# rooftop_reflector_v1_2.net
KiCad netlist of a schematic drawn in EAGLE
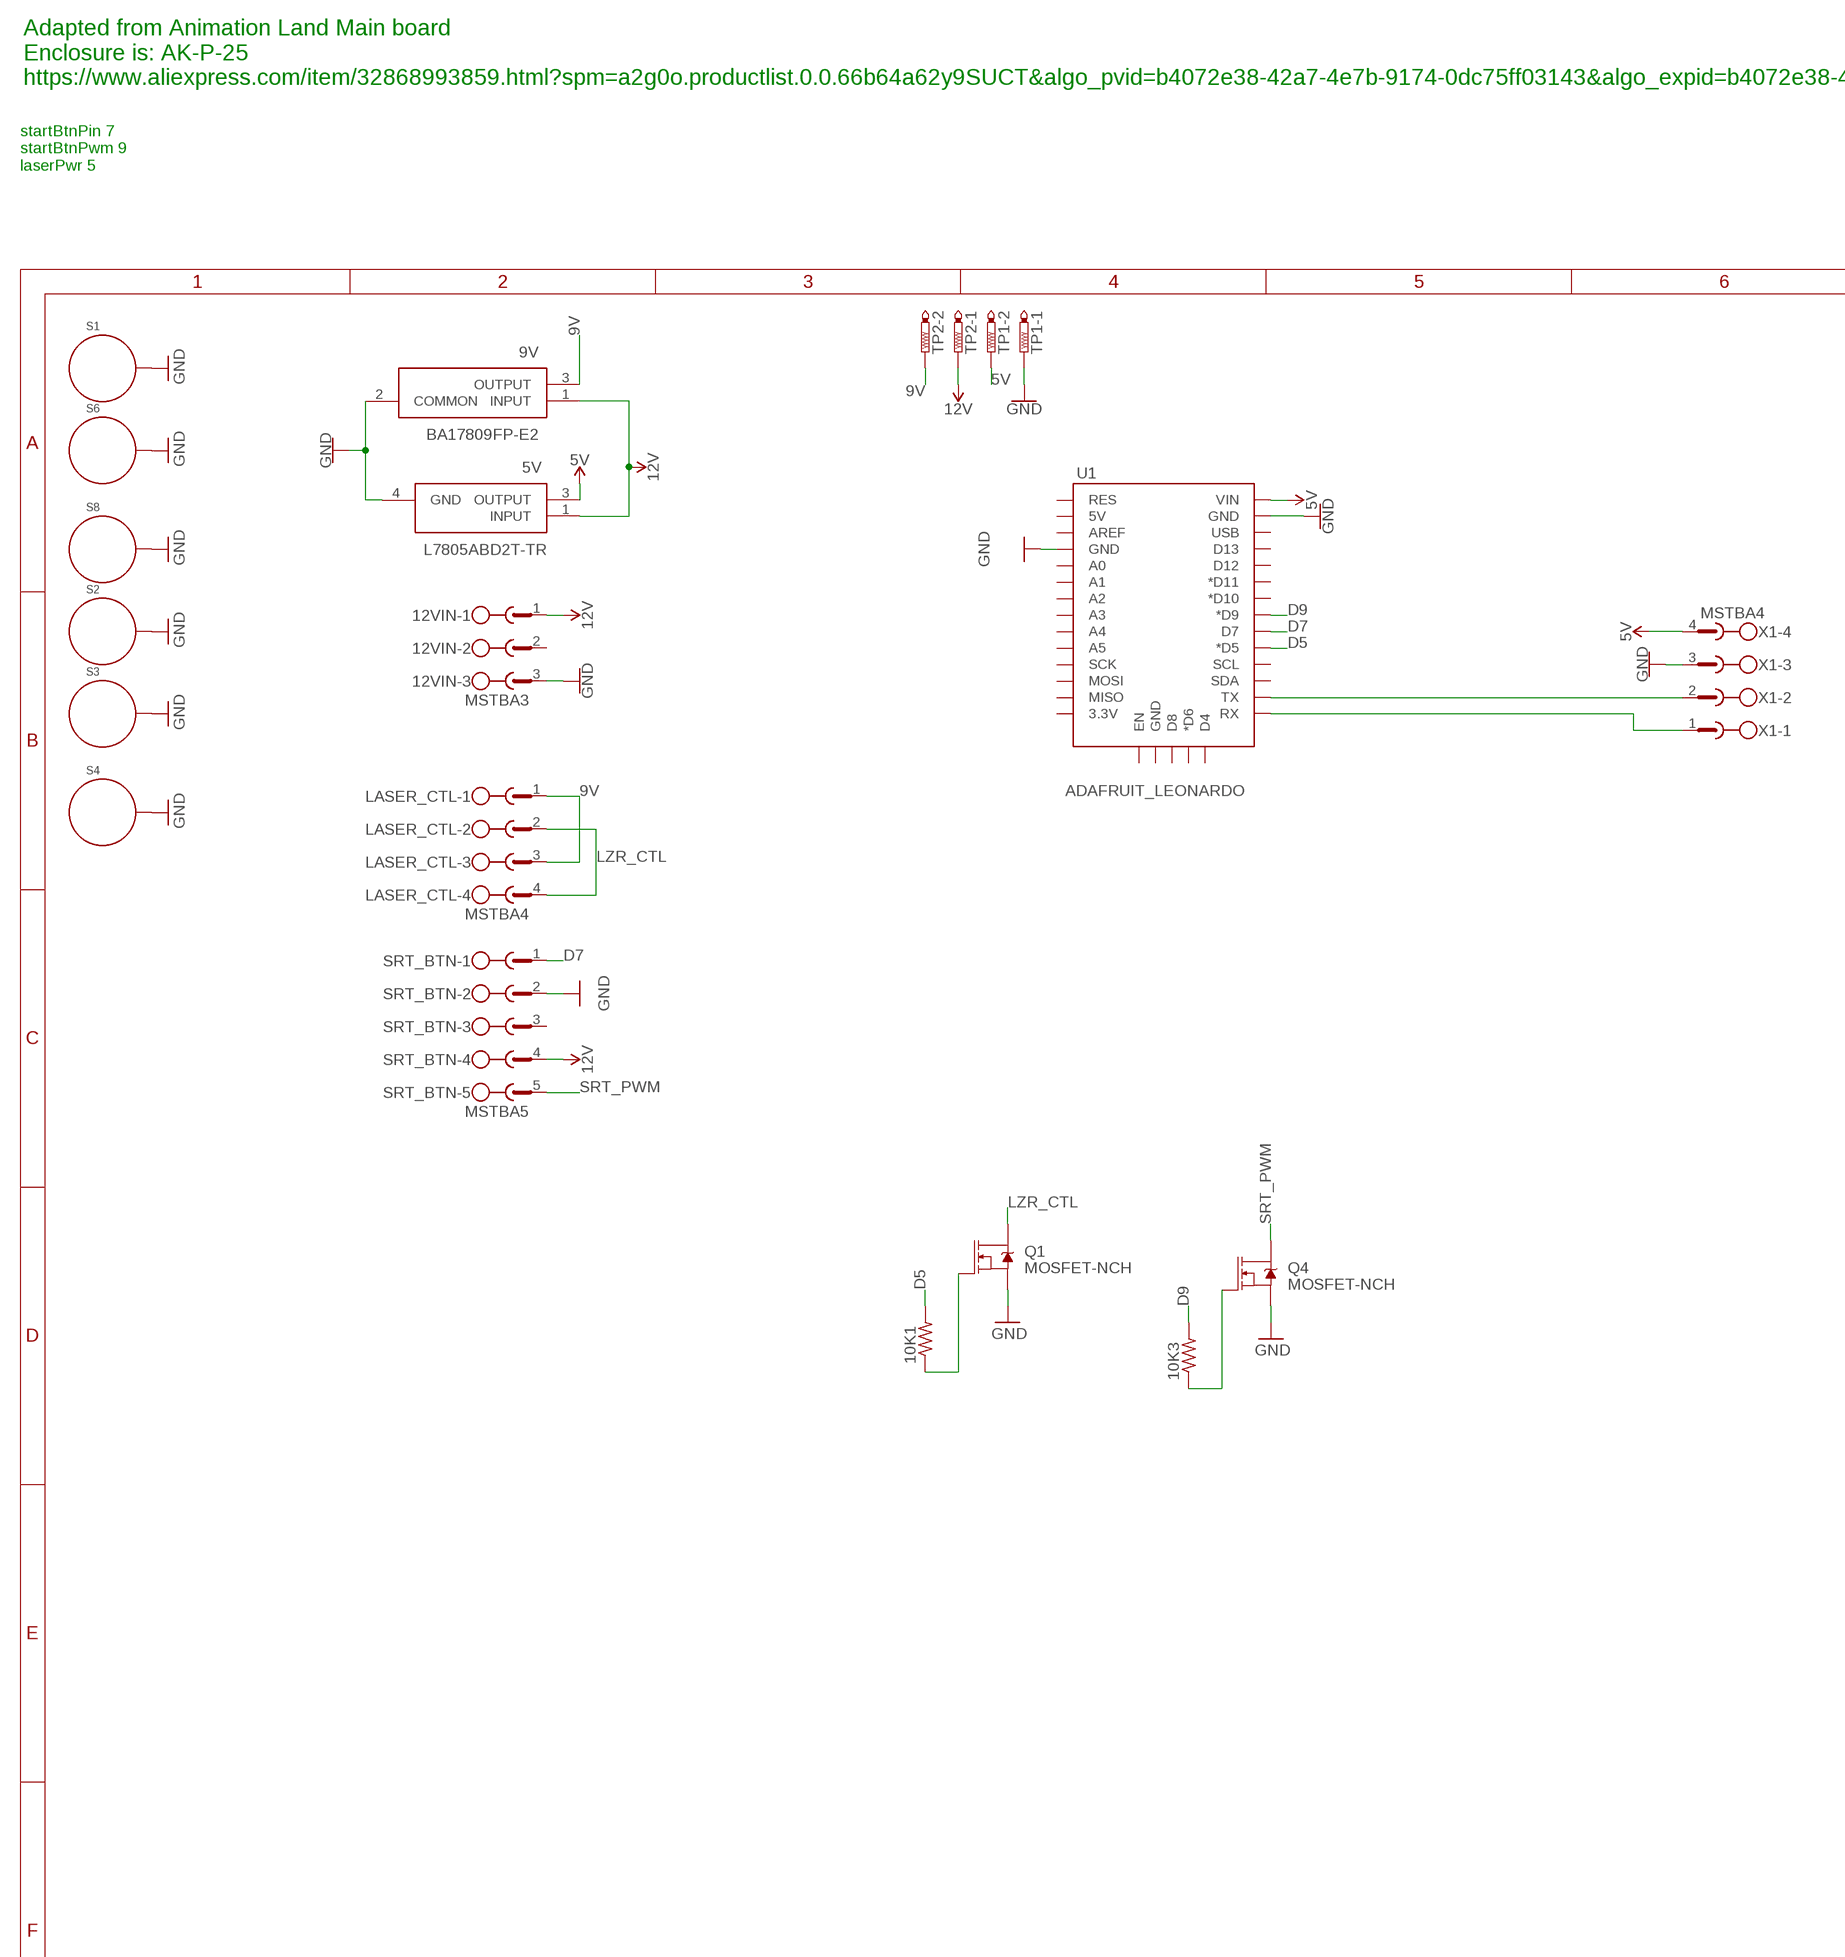
[diagram p0: schematic, sheet 1, part 1 of 2]
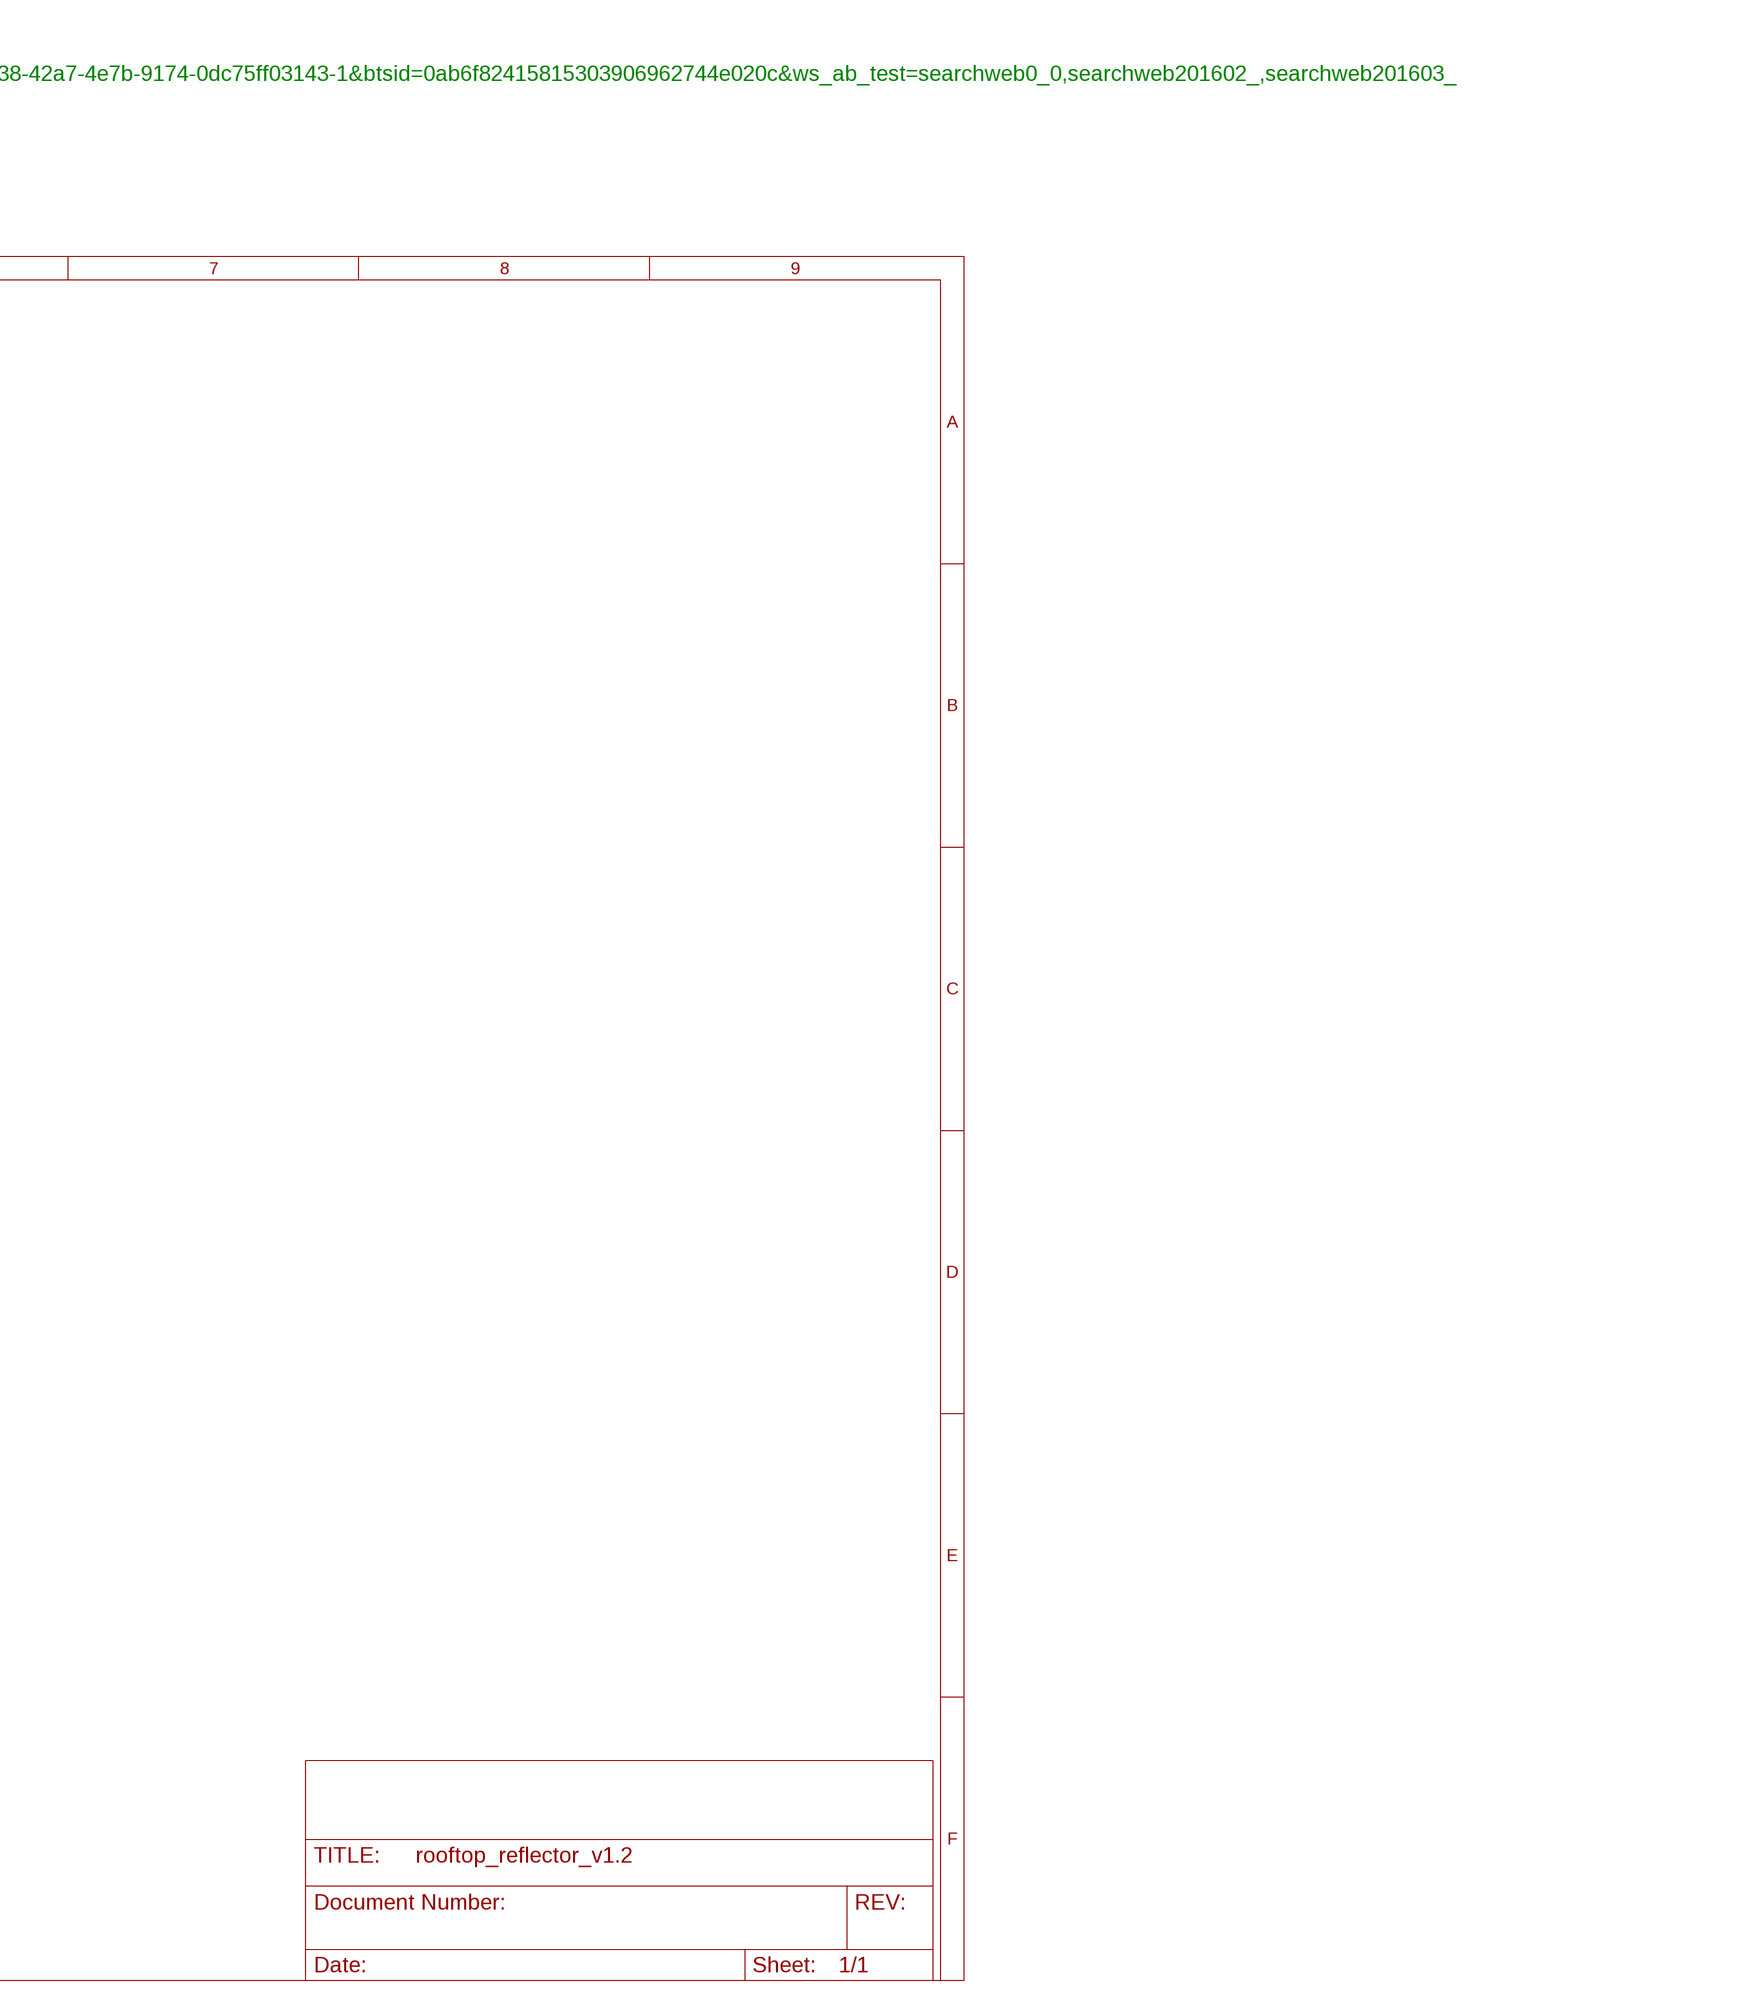
[diagram p1: schematic, sheet 1, part 2 of 2]

(export (version "E")
  (design (tool "Eeschema 10.0.6"))
  (components
    (comp (ref "5V")
      (value "L7805ABD2T-TR")
      (footprint "eagle-import:D2PAK-STB35NF10T4")
      (fields (field (name "MOUSER_PART_NUMBER") "511-L7805ABD2T-TR"))
      (libsource (lib "eagle-import") (part "L7805ABD2T-TR"))
    )
    (comp (ref "9V")
      (value "BA17809FP-E2")
      (footprint "eagle-import:BA17809FPE2")
      (fields (field (name "MOUSER_PART_NUMBER") "755-BA17809FP-E2"))
      (libsource (lib "eagle-import") (part "BA17809FP-E2"))
    )
    (comp (ref "10K1")
      (value "R-US_M0805")
      (footprint "eagle-import:M0805")
      (libsource (lib "eagle-import") (part "R-US_M0805"))
    )
    (comp (ref "10K3")
      (value "R-US_M0805")
      (footprint "eagle-import:M0805")
      (libsource (lib "eagle-import") (part "R-US_M0805"))
    )
    (comp (ref "12VIN")
      (value "MSTBA3")
      (footprint "eagle-import:MSTBA3")
      (fields (field (name "MF") "FARNELL") (field (name "MPN") "1757255"))
      (libsource (lib "eagle-import") (part "MSTBA3"))
    )
    (comp (ref "LASER_CTL")
      (value "MSTBA4")
      (footprint "eagle-import:MSTBA4")
      (fields (field (name "MF") "FARNELL") (field (name "MPN") "1757268"))
      (libsource (lib "eagle-import") (part "MSTBA4"))
    )
    (comp (ref "Q1")
      (value "MOSFET-NCH")
      (footprint "eagle-import:SO-8_POWER_PAK")
      (libsource (lib "eagle-import") (part "MOSFET-NCH"))
    )
    (comp (ref "Q4")
      (value "MOSFET-NCH")
      (footprint "eagle-import:SO-8_POWER_PAK")
      (libsource (lib "eagle-import") (part "MOSFET-NCH"))
    )
    (comp (ref "S1")
      (value "STANDOFF_ELECTRICAL5-32")
      (footprint "eagle-import:STANDOFF_ELECTRICAL_5_32")
      (libsource (lib "eagle-import") (part "STANDOFF_ELECTRICAL5-32"))
    )
    (comp (ref "S2")
      (value "STANDOFF_ELECTRICAL5-32")
      (footprint "eagle-import:STANDOFF_ELECTRICAL_5_32")
      (libsource (lib "eagle-import") (part "STANDOFF_ELECTRICAL5-32"))
    )
    (comp (ref "S3")
      (value "STANDOFF_ELECTRICAL5-32")
      (footprint "eagle-import:STANDOFF_ELECTRICAL_5_32")
      (libsource (lib "eagle-import") (part "STANDOFF_ELECTRICAL5-32"))
    )
    (comp (ref "S4")
      (value "STANDOFF_ELECTRICAL5-32")
      (footprint "eagle-import:STANDOFF_ELECTRICAL_5_32")
      (libsource (lib "eagle-import") (part "STANDOFF_ELECTRICAL5-32"))
    )
    (comp (ref "S6")
      (value "STANDOFF_ELECTRICAL5-32")
      (footprint "eagle-import:STANDOFF_ELECTRICAL_5_32")
      (libsource (lib "eagle-import") (part "STANDOFF_ELECTRICAL5-32"))
    )
    (comp (ref "S8")
      (value "STANDOFF_ELECTRICAL5-32")
      (footprint "eagle-import:STANDOFF_ELECTRICAL_5_32")
      (libsource (lib "eagle-import") (part "STANDOFF_ELECTRICAL5-32"))
    )
    (comp (ref "SRT_BTN")
      (value "MSTBA5")
      (footprint "eagle-import:MSTBA5")
      (fields (field (name "MPN") "1757271"))
      (libsource (lib "eagle-import") (part "MSTBA5"))
    )
    (comp (ref "TP1")
      (value "PTR2")
      (footprint "eagle-import:P2-38-17")
      (libsource (lib "eagle-import") (part "PTR2"))
    )
    (comp (ref "TP2")
      (value "PTR2")
      (footprint "eagle-import:P2-38-17")
      (libsource (lib "eagle-import") (part "PTR2"))
    )
    (comp (ref "U1")
      (value "ADAFRUIT_LEONARDO")
      (footprint "eagle-import:ADAFRUIT_LENOARDO")
      (libsource (lib "eagle-import") (part "ADAFRUIT_LEONARDO"))
    )
    (comp (ref "X1")
      (value "MSTBA4")
      (footprint "eagle-import:MSTBA4")
      (fields (field (name "MF") "FARNELL") (field (name "MPN") "1757268"))
      (libsource (lib "eagle-import") (part "MSTBA4"))
    )
  )
  (nets
    (net (code "1") (name "/9V") (class "Default")
      (node (ref "9V") (pin "3") (pinfunction "OUTPUT_3") (pintype "bidirectional"))
      (node (ref "LASER_CTL") (pin "1") (pinfunction "1_1") (pintype "passive"))
      (node (ref "LASER_CTL") (pin "3") (pinfunction "1_3") (pintype "passive"))
      (node (ref "TP2") (pin "TP-2") (pinfunction "TP_TP-2") (pintype "input"))
    )
    (net (code "2") (name "/D5") (class "Default")
      (node (ref "10K1") (pin "2") (pinfunction "2_2") (pintype "passive"))
      (node (ref "U1") (pin "D5") (pinfunction "*D5_D5") (pintype "bidirectional"))
    )
    (net (code "3") (name "/D7") (class "Default")
      (node (ref "SRT_BTN") (pin "1") (pinfunction "1_1") (pintype "passive"))
      (node (ref "U1") (pin "D7") (pinfunction "D7_D7") (pintype "bidirectional"))
    )
    (net (code "4") (name "/D9") (class "Default")
      (node (ref "10K3") (pin "2") (pinfunction "2_2") (pintype "passive"))
      (node (ref "U1") (pin "D9") (pinfunction "*D9_D9") (pintype "bidirectional"))
    )
    (net (code "5") (name "/LZR_CTL") (class "Default")
      (node (ref "LASER_CTL") (pin "2") (pinfunction "1_2") (pintype "passive"))
      (node (ref "LASER_CTL") (pin "4") (pinfunction "1_4") (pintype "passive"))
      (node (ref "Q1") (pin "D1") (pinfunction "D_D1") (pintype "bidirectional"))
    )
    (net (code "6") (name "/SRT_PWM") (class "Default")
      (node (ref "Q4") (pin "D1") (pinfunction "D_D1") (pintype "bidirectional"))
      (node (ref "SRT_BTN") (pin "5") (pinfunction "1_5") (pintype "passive"))
    )
    (net (code "7") (name "5V") (class "Default")
      (node (ref "5V") (pin "3") (pinfunction "OUTPUT_3") (pintype "bidirectional"))
      (node (ref "TP1") (pin "TP-2") (pinfunction "TP_TP-2") (pintype "input"))
      (node (ref "U1") (pin "VIN") (pinfunction "VIN_VIN") (pintype "bidirectional"))
      (node (ref "X1") (pin "4") (pinfunction "1_4") (pintype "passive"))
    )
    (net (code "8") (name "12V") (class "Default")
      (node (ref "12VIN") (pin "1") (pinfunction "1_1") (pintype "passive"))
      (node (ref "5V") (pin "1") (pinfunction "INPUT_1") (pintype "bidirectional"))
      (node (ref "9V") (pin "1") (pinfunction "INPUT_1") (pintype "bidirectional"))
      (node (ref "SRT_BTN") (pin "4") (pinfunction "1_4") (pintype "passive"))
      (node (ref "TP2") (pin "TP-1") (pinfunction "TP_TP-1") (pintype "input"))
    )
    (net (code "9") (name "GND") (class "Default")
      (node (ref "12VIN") (pin "3") (pinfunction "1_3") (pintype "passive"))
      (node (ref "5V") (pin "4") (pinfunction "GND_4") (pintype "bidirectional"))
      (node (ref "9V") (pin "2") (pinfunction "COMMON_2") (pintype "bidirectional"))
      (node (ref "Q1") (pin "S") (pinfunction "S_S") (pintype "bidirectional"))
      (node (ref "Q4") (pin "S") (pinfunction "S_S") (pintype "bidirectional"))
      (node (ref "S1") (pin "P1") (pinfunction "P$1_P1") (pintype "bidirectional"))
      (node (ref "S2") (pin "P1") (pinfunction "P$1_P1") (pintype "bidirectional"))
      (node (ref "S3") (pin "P1") (pinfunction "P$1_P1") (pintype "bidirectional"))
      (node (ref "S4") (pin "P1") (pinfunction "P$1_P1") (pintype "bidirectional"))
      (node (ref "S6") (pin "P1") (pinfunction "P$1_P1") (pintype "bidirectional"))
      (node (ref "S8") (pin "P1") (pinfunction "P$1_P1") (pintype "bidirectional"))
      (node (ref "SRT_BTN") (pin "2") (pinfunction "1_2") (pintype "passive"))
      (node (ref "TP1") (pin "TP-1") (pinfunction "TP_TP-1") (pintype "input"))
      (node (ref "U1") (pin "GND@0") (pinfunction "GND_GND@0") (pintype "bidirectional"))
      (node (ref "U1") (pin "GND@2") (pinfunction "GND_GND@2") (pintype "bidirectional"))
      (node (ref "X1") (pin "3") (pinfunction "1_3") (pintype "passive"))
    )
    (net (code "10") (name "Net-(10K1-Pad1)") (class "Default")
      (node (ref "10K1") (pin "1") (pinfunction "1_1") (pintype "passive"))
      (node (ref "Q1") (pin "G") (pinfunction "G_G") (pintype "bidirectional"))
    )
    (net (code "11") (name "Net-(10K3-Pad1)") (class "Default")
      (node (ref "10K3") (pin "1") (pinfunction "1_1") (pintype "passive"))
      (node (ref "Q4") (pin "G") (pinfunction "G_G") (pintype "bidirectional"))
    )
    (net (code "12") (name "Net-(U1-PadRX)") (class "Default")
      (node (ref "U1") (pin "RX") (pinfunction "RX_RX") (pintype "bidirectional"))
      (node (ref "X1") (pin "1") (pinfunction "1_1") (pintype "passive"))
    )
    (net (code "13") (name "Net-(X1B-1)") (class "Default")
      (node (ref "U1") (pin "TX") (pinfunction "TX_TX") (pintype "bidirectional"))
      (node (ref "X1") (pin "2") (pinfunction "1_2") (pintype "passive"))
    )
    (net (code "14") (name "unconnected-(12VINB-1-Pad2)") (class "Default")
      (node (ref "12VIN") (pin "2") (pinfunction "1_2") (pintype "passive"))
    )
    (net (code "15") (name "unconnected-(SRT_BTNC-1-Pad3)") (class "Default")
      (node (ref "SRT_BTN") (pin "3") (pinfunction "1_3") (pintype "passive"))
    )
    (net (code "16") (name "unconnected-(U1-*D6-PadD6)") (class "Default")
      (node (ref "U1") (pin "D6") (pinfunction "*D6_D6") (pintype "bidirectional"))
    )
    (net (code "17") (name "unconnected-(U1-*D10-PadD10)") (class "Default")
      (node (ref "U1") (pin "D10") (pinfunction "*D10_D10") (pintype "bidirectional"))
    )
    (net (code "18") (name "unconnected-(U1-*D11-PadD11)") (class "Default")
      (node (ref "U1") (pin "D11") (pinfunction "*D11_D11") (pintype "bidirectional"))
    )
    (net (code "19") (name "unconnected-(U1-3.3V-Pad3V)") (class "Default")
      (node (ref "U1") (pin "3V") (pinfunction "3.3V_3V") (pintype "bidirectional"))
    )
    (net (code "20") (name "unconnected-(U1-GND-PadGND@1)") (class "Default")
      (node (ref "U1") (pin "GND@1") (pinfunction "GND_GND@1") (pintype "bidirectional"))
    )
    (net (code "21") (name "unconnected-(U1-Pad5V)") (class "Default")
      (node (ref "U1") (pin "5V") (pinfunction "5V_5V") (pintype "bidirectional"))
    )
    (net (code "22") (name "unconnected-(U1-PadA0)") (class "Default")
      (node (ref "U1") (pin "A0") (pinfunction "A0_A0") (pintype "bidirectional"))
    )
    (net (code "23") (name "unconnected-(U1-PadA1)") (class "Default")
      (node (ref "U1") (pin "A1") (pinfunction "A1_A1") (pintype "bidirectional"))
    )
    (net (code "24") (name "unconnected-(U1-PadA2)") (class "Default")
      (node (ref "U1") (pin "A2") (pinfunction "A2_A2") (pintype "bidirectional"))
    )
    (net (code "25") (name "unconnected-(U1-PadA3)") (class "Default")
      (node (ref "U1") (pin "A3") (pinfunction "A3_A3") (pintype "bidirectional"))
    )
    (net (code "26") (name "unconnected-(U1-PadA4)") (class "Default")
      (node (ref "U1") (pin "A4") (pinfunction "A4_A4") (pintype "bidirectional"))
    )
    (net (code "27") (name "unconnected-(U1-PadA5)") (class "Default")
      (node (ref "U1") (pin "A5") (pinfunction "A5_A5") (pintype "bidirectional"))
    )
    (net (code "28") (name "unconnected-(U1-PadAREF)") (class "Default")
      (node (ref "U1") (pin "AREF") (pinfunction "AREF_AREF") (pintype "bidirectional"))
    )
    (net (code "29") (name "unconnected-(U1-PadD4)") (class "Default")
      (node (ref "U1") (pin "D4") (pinfunction "D4_D4") (pintype "bidirectional"))
    )
    (net (code "30") (name "unconnected-(U1-PadD8)") (class "Default")
      (node (ref "U1") (pin "D8") (pinfunction "D8_D8") (pintype "bidirectional"))
    )
    (net (code "31") (name "unconnected-(U1-PadD12)") (class "Default")
      (node (ref "U1") (pin "D12") (pinfunction "D12_D12") (pintype "bidirectional"))
    )
    (net (code "32") (name "unconnected-(U1-PadD13)") (class "Default")
      (node (ref "U1") (pin "D13") (pinfunction "D13_D13") (pintype "bidirectional"))
    )
    (net (code "33") (name "unconnected-(U1-PadEN)") (class "Default")
      (node (ref "U1") (pin "EN") (pinfunction "EN_EN") (pintype "bidirectional"))
    )
    (net (code "34") (name "unconnected-(U1-PadMISO)") (class "Default")
      (node (ref "U1") (pin "MISO") (pinfunction "MISO_MISO") (pintype "bidirectional"))
    )
    (net (code "35") (name "unconnected-(U1-PadMOSI)") (class "Default")
      (node (ref "U1") (pin "MOSI") (pinfunction "MOSI_MOSI") (pintype "bidirectional"))
    )
    (net (code "36") (name "unconnected-(U1-PadRES)") (class "Default")
      (node (ref "U1") (pin "RES") (pinfunction "RES_RES") (pintype "bidirectional"))
    )
    (net (code "37") (name "unconnected-(U1-PadSCK)") (class "Default")
      (node (ref "U1") (pin "SCK") (pinfunction "SCK_SCK") (pintype "bidirectional"))
    )
    (net (code "38") (name "unconnected-(U1-PadSCL)") (class "Default")
      (node (ref "U1") (pin "SCL") (pinfunction "SCL_SCL") (pintype "bidirectional"))
    )
    (net (code "39") (name "unconnected-(U1-PadSDA)") (class "Default")
      (node (ref "U1") (pin "SDA") (pinfunction "SDA_SDA") (pintype "bidirectional"))
    )
    (net (code "40") (name "unconnected-(U1-PadUSB)") (class "Default")
      (node (ref "U1") (pin "USB") (pinfunction "USB_USB") (pintype "bidirectional"))
    )
  )
)
